# TOP_HEADER_WRP.net
KiCad netlist of a schematic drawn in Altium Designer
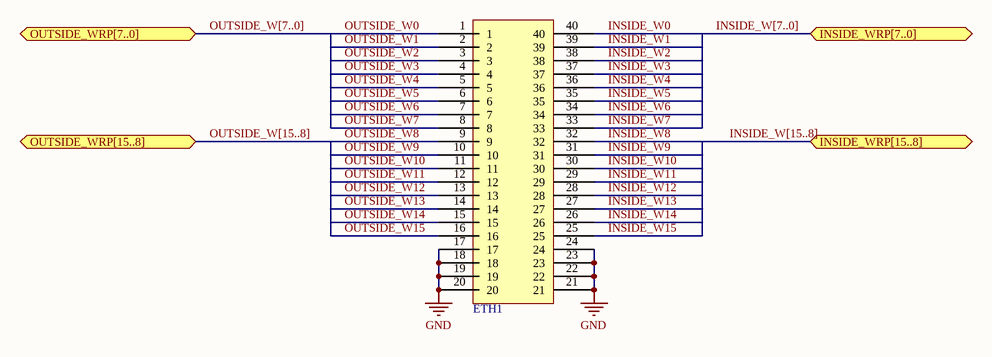
[diagram p0: TOP_HEADER_WRP.SchDoc]

(export (version "E")
  (design (tool "Eeschema 10.0.6"))
  (components
    (comp (ref "ETH1")
      (value "ADAFRUIT_HEADER")
      (footprint "FEMALE_HEADER_SMD")
      (description "Extra tall female header (SMD)")
      (libsource (lib "DUTBoard") (part "ADAFRUIT_HEADER"))
    )
  )
  (nets
    (net (code "1") (name "/INSIDE_W0") (class "Default")
      (node (ref "ETH1") (pin "40") (pinfunction "40_40") (pintype "passive"))
    )
    (net (code "2") (name "/INSIDE_W1") (class "Default")
      (node (ref "ETH1") (pin "39") (pinfunction "39_39") (pintype "passive"))
    )
    (net (code "3") (name "/INSIDE_W2") (class "Default")
      (node (ref "ETH1") (pin "38") (pinfunction "38_38") (pintype "passive"))
    )
    (net (code "4") (name "/INSIDE_W3") (class "Default")
      (node (ref "ETH1") (pin "37") (pinfunction "37_37") (pintype "passive"))
    )
    (net (code "5") (name "/INSIDE_W4") (class "Default")
      (node (ref "ETH1") (pin "36") (pinfunction "36_36") (pintype "passive"))
    )
    (net (code "6") (name "/INSIDE_W5") (class "Default")
      (node (ref "ETH1") (pin "35") (pinfunction "35_35") (pintype "passive"))
    )
    (net (code "7") (name "/INSIDE_W6") (class "Default")
      (node (ref "ETH1") (pin "34") (pinfunction "34_34") (pintype "passive"))
    )
    (net (code "8") (name "/INSIDE_W7") (class "Default")
      (node (ref "ETH1") (pin "33") (pinfunction "33_33") (pintype "passive"))
    )
    (net (code "9") (name "/INSIDE_W8") (class "Default")
      (node (ref "ETH1") (pin "32") (pinfunction "32_32") (pintype "passive"))
    )
    (net (code "10") (name "/INSIDE_W9") (class "Default")
      (node (ref "ETH1") (pin "31") (pinfunction "31_31") (pintype "passive"))
    )
    (net (code "11") (name "/INSIDE_W10") (class "Default")
      (node (ref "ETH1") (pin "30") (pinfunction "30_30") (pintype "passive"))
    )
    (net (code "12") (name "/INSIDE_W11") (class "Default")
      (node (ref "ETH1") (pin "29") (pinfunction "29_29") (pintype "passive"))
    )
    (net (code "13") (name "/INSIDE_W12") (class "Default")
      (node (ref "ETH1") (pin "28") (pinfunction "28_28") (pintype "passive"))
    )
    (net (code "14") (name "/INSIDE_W13") (class "Default")
      (node (ref "ETH1") (pin "27") (pinfunction "27_27") (pintype "passive"))
    )
    (net (code "15") (name "/INSIDE_W14") (class "Default")
      (node (ref "ETH1") (pin "26") (pinfunction "26_26") (pintype "passive"))
    )
    (net (code "16") (name "/INSIDE_W15") (class "Default")
      (node (ref "ETH1") (pin "25") (pinfunction "25_25") (pintype "passive"))
    )
    (net (code "19") (name "/OUTSIDE_W0") (class "Default")
      (node (ref "ETH1") (pin "1") (pinfunction "1_1") (pintype "passive"))
    )
    (net (code "20") (name "/OUTSIDE_W1") (class "Default")
      (node (ref "ETH1") (pin "2") (pinfunction "2_2") (pintype "passive"))
    )
    (net (code "21") (name "/OUTSIDE_W2") (class "Default")
      (node (ref "ETH1") (pin "3") (pinfunction "3_3") (pintype "passive"))
    )
    (net (code "22") (name "/OUTSIDE_W3") (class "Default")
      (node (ref "ETH1") (pin "4") (pinfunction "4_4") (pintype "passive"))
    )
    (net (code "23") (name "/OUTSIDE_W4") (class "Default")
      (node (ref "ETH1") (pin "5") (pinfunction "5_5") (pintype "passive"))
    )
    (net (code "24") (name "/OUTSIDE_W5") (class "Default")
      (node (ref "ETH1") (pin "6") (pinfunction "6_6") (pintype "passive"))
    )
    (net (code "25") (name "/OUTSIDE_W6") (class "Default")
      (node (ref "ETH1") (pin "7") (pinfunction "7_7") (pintype "passive"))
    )
    (net (code "26") (name "/OUTSIDE_W7") (class "Default")
      (node (ref "ETH1") (pin "8") (pinfunction "8_8") (pintype "passive"))
    )
    (net (code "27") (name "/OUTSIDE_W8") (class "Default")
      (node (ref "ETH1") (pin "9") (pinfunction "9_9") (pintype "passive"))
    )
    (net (code "28") (name "/OUTSIDE_W9") (class "Default")
      (node (ref "ETH1") (pin "10") (pinfunction "10_10") (pintype "passive"))
    )
    (net (code "29") (name "/OUTSIDE_W10") (class "Default")
      (node (ref "ETH1") (pin "11") (pinfunction "11_11") (pintype "passive"))
    )
    (net (code "30") (name "/OUTSIDE_W11") (class "Default")
      (node (ref "ETH1") (pin "12") (pinfunction "12_12") (pintype "passive"))
    )
    (net (code "31") (name "/OUTSIDE_W12") (class "Default")
      (node (ref "ETH1") (pin "13") (pinfunction "13_13") (pintype "passive"))
    )
    (net (code "32") (name "/OUTSIDE_W13") (class "Default")
      (node (ref "ETH1") (pin "14") (pinfunction "14_14") (pintype "passive"))
    )
    (net (code "33") (name "/OUTSIDE_W14") (class "Default")
      (node (ref "ETH1") (pin "15") (pinfunction "15_15") (pintype "passive"))
    )
    (net (code "34") (name "/OUTSIDE_W15") (class "Default")
      (node (ref "ETH1") (pin "16") (pinfunction "16_16") (pintype "passive"))
    )
    (net (code "37") (name "GND") (class "Default")
      (node (ref "ETH1") (pin "17") (pinfunction "17_17") (pintype "passive"))
      (node (ref "ETH1") (pin "18") (pinfunction "18_18") (pintype "passive"))
      (node (ref "ETH1") (pin "19") (pinfunction "19_19") (pintype "passive"))
      (node (ref "ETH1") (pin "20") (pinfunction "20_20") (pintype "passive"))
      (node (ref "ETH1") (pin "21") (pinfunction "21_21") (pintype "passive"))
      (node (ref "ETH1") (pin "22") (pinfunction "22_22") (pintype "passive"))
      (node (ref "ETH1") (pin "23") (pinfunction "23_23") (pintype "passive"))
      (node (ref "ETH1") (pin "24") (pinfunction "24_24") (pintype "passive"))
    )
  )
)
